# LM2596-4.net
KiCad netlist of a schematic drawn in Altium Designer
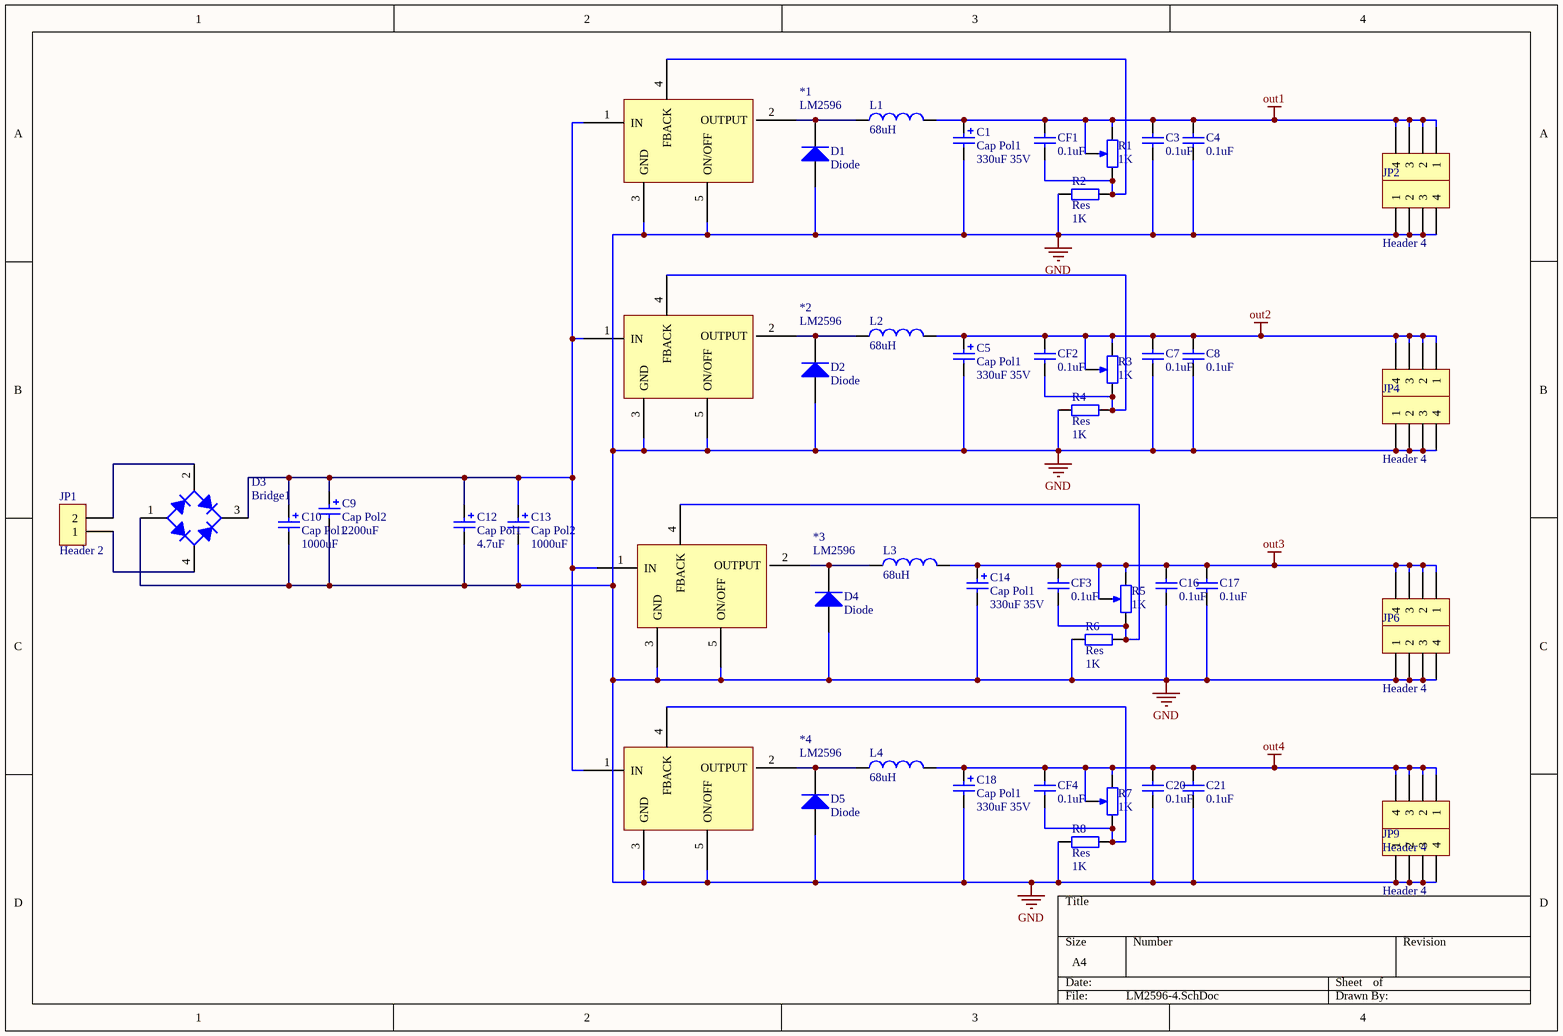
[diagram p0: LM2596-4.SchDoc]

(export (version "E")
  (design (tool "Eeschema 10.0.6"))
  (components
    (comp (ref "*1") (value "LM2596") (footprint "HDR1-5") (libsource (lib "HGH") (part "LM2596")))
    (comp (ref "*2") (value "LM2596") (footprint "HDR1-5") (libsource (lib "HGH") (part "LM2596")))
    (comp (ref "*3") (value "LM2596") (footprint "HDR1-5") (libsource (lib "HGH") (part "LM2596")))
    (comp (ref "*4") (value "LM2596") (footprint "HDR1-5") (libsource (lib "HGH") (part "LM2596")))
    (comp (ref "C1")
      (value "Cap Pol1")
      (footprint "RB0.3-0.65")
      (description "Polarized Capacitor (Radial)")
      (fields
        (field (name "MANUFACTURER") "Generic Components")
        (field (name "ALTIUM_VALUE") "330uF 35V")
        (field (name "PUBLISHER") "Altium Hobart Technology Centre")
      )
      (libsource (lib "HGH") (part "Cap Pol1"))
    )
    (comp (ref "C3")
      (value "0.1uF")
      (footprint "CC1005-0402")
      (description "Capacitor")
      (fields
        (field (name "MANUFACTURER") "Generic Components")
        (field (name "Comment") "CAP")
        (field (name "PUBLISHER") "Altium Hobart Technology Centre")
      )
      (libsource (lib "HGH") (part "CAP"))
    )
    (comp (ref "C4")
      (value "0.1uF")
      (footprint "CC1005-0402")
      (description "Capacitor")
      (fields
        (field (name "MANUFACTURER") "Generic Components")
        (field (name "Comment") "CAP")
        (field (name "PUBLISHER") "Altium Hobart Technology Centre")
      )
      (libsource (lib "HGH") (part "CAP"))
    )
    (comp (ref "C5")
      (value "Cap Pol1")
      (footprint "RB0.3-0.65")
      (description "Polarized Capacitor (Radial)")
      (fields
        (field (name "MANUFACTURER") "Generic Components")
        (field (name "ALTIUM_VALUE") "330uF 35V")
        (field (name "PUBLISHER") "Altium Hobart Technology Centre")
      )
      (libsource (lib "HGH") (part "Cap Pol1"))
    )
    (comp (ref "C7")
      (value "0.1uF")
      (footprint "CC1005-0402")
      (description "Capacitor")
      (fields
        (field (name "MANUFACTURER") "Generic Components")
        (field (name "Comment") "CAP")
        (field (name "PUBLISHER") "Altium Hobart Technology Centre")
      )
      (libsource (lib "HGH") (part "CAP"))
    )
    (comp (ref "C8")
      (value "0.1uF")
      (footprint "CC1005-0402")
      (description "Capacitor")
      (fields
        (field (name "MANUFACTURER") "Generic Components")
        (field (name "Comment") "CAP")
        (field (name "PUBLISHER") "Altium Hobart Technology Centre")
      )
      (libsource (lib "HGH") (part "CAP"))
    )
    (comp (ref "C9")
      (value "Cap Pol2")
      (footprint "RB0.3-0.65")
      (description "Polarized Capacitor (Axial)")
      (fields
        (field (name "MANUFACTURER") "Generic Components")
        (field (name "ALTIUM_VALUE") "2200uF")
        (field (name "PUBLISHER") "Altium Hobart Technology Centre")
      )
      (libsource (lib "HGH") (part "Cap Pol2"))
    )
    (comp (ref "C10")
      (value "Cap Pol1")
      (footprint "RB0.3-0.65")
      (description "Polarized Capacitor (Radial)")
      (fields
        (field (name "MANUFACTURER") "Generic Components")
        (field (name "ALTIUM_VALUE") "1000uF")
        (field (name "PUBLISHER") "Altium Hobart Technology Centre")
      )
      (libsource (lib "HGH") (part "Cap Pol1"))
    )
    (comp (ref "C12")
      (value "Cap Pol1")
      (footprint "R-0805")
      (description "Polarized Capacitor (Radial)")
      (fields
        (field (name "MANUFACTURER") "Generic Components")
        (field (name "ALTIUM_VALUE") "4.7uF")
        (field (name "PUBLISHER") "Altium Hobart Technology Centre")
      )
      (libsource (lib "HGH") (part "Cap Pol1"))
    )
    (comp (ref "C13")
      (value "Cap Pol2")
      (footprint "RB0.2-0.50")
      (description "Polarized Capacitor (Axial)")
      (fields
        (field (name "MANUFACTURER") "Generic Components")
        (field (name "ALTIUM_VALUE") "1000uF")
        (field (name "PUBLISHER") "Altium Hobart Technology Centre")
      )
      (libsource (lib "HGH") (part "Cap Pol2"))
    )
    (comp (ref "C14")
      (value "Cap Pol1")
      (footprint "RB0.3-0.65")
      (description "Polarized Capacitor (Radial)")
      (fields
        (field (name "MANUFACTURER") "Generic Components")
        (field (name "ALTIUM_VALUE") "330uF 35V")
        (field (name "PUBLISHER") "Altium Hobart Technology Centre")
      )
      (libsource (lib "HGH") (part "Cap Pol1"))
    )
    (comp (ref "C16")
      (value "0.1uF")
      (footprint "CC1005-0402")
      (description "Capacitor")
      (fields
        (field (name "MANUFACTURER") "Generic Components")
        (field (name "Comment") "CAP")
        (field (name "PUBLISHER") "Altium Hobart Technology Centre")
      )
      (libsource (lib "HGH") (part "CAP"))
    )
    (comp (ref "C17")
      (value "0.1uF")
      (footprint "CC1005-0402")
      (description "Capacitor")
      (fields
        (field (name "MANUFACTURER") "Generic Components")
        (field (name "Comment") "CAP")
        (field (name "PUBLISHER") "Altium Hobart Technology Centre")
      )
      (libsource (lib "HGH") (part "CAP"))
    )
    (comp (ref "C18")
      (value "Cap Pol1")
      (footprint "RB0.3-0.65")
      (description "Polarized Capacitor (Radial)")
      (fields
        (field (name "MANUFACTURER") "Generic Components")
        (field (name "ALTIUM_VALUE") "330uF 35V")
        (field (name "PUBLISHER") "Altium Hobart Technology Centre")
      )
      (libsource (lib "HGH") (part "Cap Pol1"))
    )
    (comp (ref "C20")
      (value "0.1uF")
      (footprint "CC1005-0402")
      (description "Capacitor")
      (fields
        (field (name "MANUFACTURER") "Generic Components")
        (field (name "Comment") "CAP")
        (field (name "PUBLISHER") "Altium Hobart Technology Centre")
      )
      (libsource (lib "HGH") (part "CAP"))
    )
    (comp (ref "C21")
      (value "0.1uF")
      (footprint "CC1005-0402")
      (description "Capacitor")
      (fields
        (field (name "MANUFACTURER") "Generic Components")
        (field (name "Comment") "CAP")
        (field (name "PUBLISHER") "Altium Hobart Technology Centre")
      )
      (libsource (lib "HGH") (part "CAP"))
    )
    (comp (ref "CF1")
      (value "0.1uF")
      (footprint "CC1005-0402")
      (description "Capacitor")
      (fields
        (field (name "MANUFACTURER") "Generic Components")
        (field (name "Comment") "CAP")
        (field (name "PUBLISHER") "Altium Hobart Technology Centre")
      )
      (libsource (lib "HGH") (part "CAP"))
    )
    (comp (ref "CF2")
      (value "0.1uF")
      (footprint "CC1005-0402")
      (description "Capacitor")
      (fields
        (field (name "MANUFACTURER") "Generic Components")
        (field (name "Comment") "CAP")
        (field (name "PUBLISHER") "Altium Hobart Technology Centre")
      )
      (libsource (lib "HGH") (part "CAP"))
    )
    (comp (ref "CF3")
      (value "0.1uF")
      (footprint "CC1005-0402")
      (description "Capacitor")
      (fields
        (field (name "MANUFACTURER") "Generic Components")
        (field (name "Comment") "CAP")
        (field (name "PUBLISHER") "Altium Hobart Technology Centre")
      )
      (libsource (lib "HGH") (part "CAP"))
    )
    (comp (ref "CF4")
      (value "0.1uF")
      (footprint "CC1005-0402")
      (description "Capacitor")
      (fields
        (field (name "MANUFACTURER") "Generic Components")
        (field (name "Comment") "CAP")
        (field (name "PUBLISHER") "Altium Hobart Technology Centre")
      )
      (libsource (lib "HGH") (part "CAP"))
    )
    (comp (ref "D1")
      (value "Diode")
      (footprint "Diode-5817")
      (description "Default Diode")
      (fields
        (field (name "MANUFACTURER") "Generic Components")
        (field (name "PUBLISHER") "Altium Hobart Technology Centre")
      )
      (libsource (lib "HGH") (part "Diode"))
    )
    (comp (ref "D2")
      (value "Diode")
      (footprint "Diode-5817")
      (description "Default Diode")
      (fields
        (field (name "MANUFACTURER") "Generic Components")
        (field (name "PUBLISHER") "Altium Hobart Technology Centre")
      )
      (libsource (lib "HGH") (part "Diode"))
    )
    (comp (ref "D3")
      (value "Bridge1")
      (footprint "qiao")
      (description "Full Wave Diode Bridge")
      (fields
        (field (name "MANUFACTURER") "Generic Components")
        (field (name "PUBLISHER") "Altium Hobart Technology Centre")
      )
      (libsource (lib "HGH") (part "Bridge1"))
    )
    (comp (ref "D4")
      (value "Diode")
      (footprint "Diode-5817")
      (description "Default Diode")
      (fields
        (field (name "MANUFACTURER") "Generic Components")
        (field (name "PUBLISHER") "Altium Hobart Technology Centre")
      )
      (libsource (lib "HGH") (part "Diode"))
    )
    (comp (ref "D5")
      (value "Diode")
      (footprint "Diode-5817")
      (description "Default Diode")
      (fields
        (field (name "MANUFACTURER") "Generic Components")
        (field (name "PUBLISHER") "Altium Hobart Technology Centre")
      )
      (libsource (lib "HGH") (part "Diode"))
    )
    (comp (ref "JP1")
      (value "Header 2")
      (footprint "H-2/2")
      (description "Header, 2-Pin")
      (fields (field (name "MANUFACTURER") "Generic Components"))
      (libsource (lib "HGH") (part "Header 2"))
    )
    (comp (ref "JP2")
      (value "Header 4")
      (footprint "HDR1-4")
      (description "Header, 4-Pin")
      (fields (field (name "MANUFACTURER") "Generic Components"))
      (libsource (lib "My SchLib") (part "Header 4"))
    )
    (comp (ref "JP3")
      (value "Header 4")
      (footprint "HDR1-4")
      (description "Header, 4-Pin")
      (fields (field (name "MANUFACTURER") "Generic Components"))
      (libsource (lib "") (part "Header 4_1"))
    )
    (comp (ref "JP4")
      (value "Header 4")
      (footprint "HDR1-4")
      (description "Header, 4-Pin")
      (fields (field (name "MANUFACTURER") "Generic Components"))
      (libsource (lib "My SchLib") (part "Header 4"))
    )
    (comp (ref "JP5")
      (value "Header 4")
      (footprint "HDR1-4")
      (description "Header, 4-Pin")
      (fields (field (name "MANUFACTURER") "Generic Components"))
      (libsource (lib "") (part "Header 4_1"))
    )
    (comp (ref "JP6")
      (value "Header 4")
      (footprint "HDR1-4")
      (description "Header, 4-Pin")
      (fields (field (name "MANUFACTURER") "Generic Components"))
      (libsource (lib "My SchLib") (part "Header 4"))
    )
    (comp (ref "JP7")
      (value "Header 4")
      (footprint "HDR1-4")
      (description "Header, 4-Pin")
      (fields (field (name "MANUFACTURER") "Generic Components"))
      (libsource (lib "") (part "Header 4_1"))
    )
    (comp (ref "JP8")
      (value "Header 4")
      (footprint "HDR1-4")
      (description "Header, 4-Pin")
      (fields (field (name "MANUFACTURER") "Generic Components"))
      (libsource (lib "My SchLib") (part "Header 4"))
    )
    (comp (ref "JP9")
      (value "Header 4")
      (footprint "HDR1-4")
      (description "Header, 4-Pin")
      (fields (field (name "MANUFACTURER") "Generic Components"))
      (libsource (lib "") (part "Header 4_1"))
    )
    (comp (ref "L1")
      (value "68uH")
      (footprint "RBL0.2")
      (description "Inductor")
      (fields
        (field (name "MANUFACTURER") "Generic Components")
        (field (name "Comment") "INDUCTOT")
        (field (name "PUBLISHER") "Altium Hobart Technology Centre")
      )
      (libsource (lib "HGH") (part "INDUCTOT"))
    )
    (comp (ref "L2")
      (value "68uH")
      (footprint "RBL0.2")
      (description "Inductor")
      (fields
        (field (name "MANUFACTURER") "Generic Components")
        (field (name "Comment") "INDUCTOT")
        (field (name "PUBLISHER") "Altium Hobart Technology Centre")
      )
      (libsource (lib "HGH") (part "INDUCTOT"))
    )
    (comp (ref "L3")
      (value "68uH")
      (footprint "RBL0.2")
      (description "Inductor")
      (fields
        (field (name "MANUFACTURER") "Generic Components")
        (field (name "Comment") "INDUCTOT")
        (field (name "PUBLISHER") "Altium Hobart Technology Centre")
      )
      (libsource (lib "HGH") (part "INDUCTOT"))
    )
    (comp (ref "L4")
      (value "68uH")
      (footprint "RBL0.2")
      (description "Inductor")
      (fields
        (field (name "MANUFACTURER") "Generic Components")
        (field (name "Comment") "INDUCTOT")
        (field (name "PUBLISHER") "Altium Hobart Technology Centre")
      )
      (libsource (lib "HGH") (part "INDUCTOT"))
    )
    (comp (ref "R1")
      (value "1K")
      (footprint "VR-S")
      (description "Potentiometer")
      (fields (field (name "Comment") "RES-Pot2"))
      (libsource (lib "HGH") (part "RES-Pot2"))
    )
    (comp (ref "R2")
      (value "Res")
      (footprint "1n4148")
      (description "Resistor")
      (fields
        (field (name "MANUFACTURER") "Generic Components")
        (field (name "ALTIUM_VALUE") "1K")
        (field (name "PUBLISHER") "Altium Hobart Technology Centre")
      )
      (libsource (lib "HGH") (part "Res"))
    )
    (comp (ref "R3")
      (value "1K")
      (footprint "VR-S")
      (description "Potentiometer")
      (fields (field (name "Comment") "RES-Pot2"))
      (libsource (lib "HGH") (part "RES-Pot2"))
    )
    (comp (ref "R4")
      (value "Res")
      (footprint "1n4148")
      (description "Resistor")
      (fields
        (field (name "MANUFACTURER") "Generic Components")
        (field (name "ALTIUM_VALUE") "1K")
        (field (name "PUBLISHER") "Altium Hobart Technology Centre")
      )
      (libsource (lib "HGH") (part "Res"))
    )
    (comp (ref "R5")
      (value "1K")
      (footprint "VR-S")
      (description "Potentiometer")
      (fields (field (name "Comment") "RES-Pot2"))
      (libsource (lib "HGH") (part "RES-Pot2"))
    )
    (comp (ref "R6")
      (value "Res")
      (footprint "1n4148")
      (description "Resistor")
      (fields
        (field (name "MANUFACTURER") "Generic Components")
        (field (name "ALTIUM_VALUE") "1K")
        (field (name "PUBLISHER") "Altium Hobart Technology Centre")
      )
      (libsource (lib "HGH") (part "Res"))
    )
    (comp (ref "R7")
      (value "1K")
      (footprint "VR-S")
      (description "Potentiometer")
      (fields (field (name "Comment") "RES-Pot2"))
      (libsource (lib "HGH") (part "RES-Pot2"))
    )
    (comp (ref "R8")
      (value "Res")
      (footprint "1n4148")
      (description "Resistor")
      (fields
        (field (name "MANUFACTURER") "Generic Components")
        (field (name "ALTIUM_VALUE") "1K")
        (field (name "PUBLISHER") "Altium Hobart Technology Centre")
      )
      (libsource (lib "HGH") (part "Res"))
    )
  )
  (nets
    (net (code "1") (name "GND") (class "Default")
      (node (ref "*1") (pin "3") (pinfunction "GND_3") (pintype "passive"))
      (node (ref "*1") (pin "5") (pinfunction "ON/OFF_5") (pintype "passive"))
      (node (ref "*2") (pin "3") (pinfunction "GND_3") (pintype "passive"))
      (node (ref "*2") (pin "5") (pinfunction "ON/OFF_5") (pintype "passive"))
      (node (ref "*3") (pin "3") (pinfunction "GND_3") (pintype "passive"))
      (node (ref "*3") (pin "5") (pinfunction "ON/OFF_5") (pintype "passive"))
      (node (ref "*4") (pin "3") (pinfunction "GND_3") (pintype "passive"))
      (node (ref "*4") (pin "5") (pinfunction "ON/OFF_5") (pintype "passive"))
      (node (ref "C1") (pin "2") (pinfunction "2_2") (pintype "passive"))
      (node (ref "C10") (pin "2") (pinfunction "2_2") (pintype "passive"))
      (node (ref "C12") (pin "2") (pinfunction "2_2") (pintype "passive"))
      (node (ref "C13") (pin "2") (pinfunction "2_2") (pintype "passive"))
      (node (ref "C14") (pin "2") (pinfunction "2_2") (pintype "passive"))
      (node (ref "C16") (pin "1") (pinfunction "1_1") (pintype "passive"))
      (node (ref "C17") (pin "1") (pinfunction "1_1") (pintype "passive"))
      (node (ref "C18") (pin "2") (pinfunction "2_2") (pintype "passive"))
      (node (ref "C20") (pin "1") (pinfunction "1_1") (pintype "passive"))
      (node (ref "C21") (pin "1") (pinfunction "1_1") (pintype "passive"))
      (node (ref "C3") (pin "1") (pinfunction "1_1") (pintype "passive"))
      (node (ref "C4") (pin "1") (pinfunction "1_1") (pintype "passive"))
      (node (ref "C5") (pin "2") (pinfunction "2_2") (pintype "passive"))
      (node (ref "C7") (pin "1") (pinfunction "1_1") (pintype "passive"))
      (node (ref "C8") (pin "1") (pinfunction "1_1") (pintype "passive"))
      (node (ref "C9") (pin "2") (pinfunction "2_2") (pintype "passive"))
      (node (ref "D1") (pin "1") (pinfunction "A_1") (pintype "passive"))
      (node (ref "D2") (pin "1") (pinfunction "A_1") (pintype "passive"))
      (node (ref "D3") (pin "1") (pinfunction "A_1") (pintype "passive"))
      (node (ref "D4") (pin "1") (pinfunction "A_1") (pintype "passive"))
      (node (ref "D5") (pin "1") (pinfunction "A_1") (pintype "passive"))
      (node (ref "JP2") (pin "1") (pinfunction "1_1") (pintype "passive"))
      (node (ref "JP2") (pin "2") (pinfunction "2_2") (pintype "passive"))
      (node (ref "JP2") (pin "3") (pinfunction "3_3") (pintype "passive"))
      (node (ref "JP2") (pin "4") (pinfunction "4_4") (pintype "passive"))
      (node (ref "JP4") (pin "1") (pinfunction "1_1") (pintype "passive"))
      (node (ref "JP4") (pin "2") (pinfunction "2_2") (pintype "passive"))
      (node (ref "JP4") (pin "3") (pinfunction "3_3") (pintype "passive"))
      (node (ref "JP4") (pin "4") (pinfunction "4_4") (pintype "passive"))
      (node (ref "JP6") (pin "1") (pinfunction "1_1") (pintype "passive"))
      (node (ref "JP6") (pin "2") (pinfunction "2_2") (pintype "passive"))
      (node (ref "JP6") (pin "3") (pinfunction "3_3") (pintype "passive"))
      (node (ref "JP6") (pin "4") (pinfunction "4_4") (pintype "passive"))
      (node (ref "JP8") (pin "1") (pinfunction "1_1") (pintype "passive"))
      (node (ref "JP8") (pin "2") (pinfunction "2_2") (pintype "passive"))
      (node (ref "JP8") (pin "3") (pinfunction "3_3") (pintype "passive"))
      (node (ref "JP8") (pin "4") (pinfunction "4_4") (pintype "passive"))
      (node (ref "R2") (pin "2") (pinfunction "2_2") (pintype "passive"))
      (node (ref "R4") (pin "2") (pinfunction "2_2") (pintype "passive"))
      (node (ref "R6") (pin "2") (pinfunction "2_2") (pintype "passive"))
      (node (ref "R8") (pin "2") (pinfunction "2_2") (pintype "passive"))
    )
    (net (code "2") (name "Net-(*1-FBACK)") (class "Default")
      (node (ref "*1") (pin "4") (pinfunction "FBACK_4") (pintype "passive"))
      (node (ref "CF1") (pin "1") (pinfunction "1_1") (pintype "passive"))
      (node (ref "R1") (pin "1") (pinfunction "BOT_1") (pintype "passive"))
      (node (ref "R2") (pin "1") (pinfunction "1_1") (pintype "passive"))
    )
    (net (code "3") (name "Net-(*1-IN)") (class "Default")
      (node (ref "*1") (pin "1") (pinfunction "IN_1") (pintype "passive"))
      (node (ref "*2") (pin "1") (pinfunction "IN_1") (pintype "passive"))
      (node (ref "*3") (pin "1") (pinfunction "IN_1") (pintype "passive"))
      (node (ref "*4") (pin "1") (pinfunction "IN_1") (pintype "passive"))
      (node (ref "C10") (pin "1") (pinfunction "1_1") (pintype "passive"))
      (node (ref "C12") (pin "1") (pinfunction "1_1") (pintype "passive"))
      (node (ref "C13") (pin "1") (pinfunction "1_1") (pintype "passive"))
      (node (ref "C9") (pin "1") (pinfunction "1_1") (pintype "passive"))
      (node (ref "D3") (pin "3") (pinfunction "K_3") (pintype "passive"))
    )
    (net (code "4") (name "Net-(*1-OUTPUT)") (class "Default")
      (node (ref "*1") (pin "2") (pinfunction "OUTPUT_2") (pintype "passive"))
      (node (ref "D1") (pin "2") (pinfunction "K_2") (pintype "passive"))
      (node (ref "L1") (pin "1") (pinfunction "1_1") (pintype "passive"))
    )
    (net (code "5") (name "Net-(*2-FBACK)") (class "Default")
      (node (ref "*2") (pin "4") (pinfunction "FBACK_4") (pintype "passive"))
      (node (ref "CF2") (pin "1") (pinfunction "1_1") (pintype "passive"))
      (node (ref "R3") (pin "1") (pinfunction "BOT_1") (pintype "passive"))
      (node (ref "R4") (pin "1") (pinfunction "1_1") (pintype "passive"))
    )
    (net (code "6") (name "Net-(*2-OUTPUT)") (class "Default")
      (node (ref "*2") (pin "2") (pinfunction "OUTPUT_2") (pintype "passive"))
      (node (ref "D2") (pin "2") (pinfunction "K_2") (pintype "passive"))
      (node (ref "L2") (pin "1") (pinfunction "1_1") (pintype "passive"))
    )
    (net (code "7") (name "Net-(*3-FBACK)") (class "Default")
      (node (ref "*3") (pin "4") (pinfunction "FBACK_4") (pintype "passive"))
      (node (ref "CF3") (pin "1") (pinfunction "1_1") (pintype "passive"))
      (node (ref "R5") (pin "1") (pinfunction "BOT_1") (pintype "passive"))
      (node (ref "R6") (pin "1") (pinfunction "1_1") (pintype "passive"))
    )
    (net (code "8") (name "Net-(*3-OUTPUT)") (class "Default")
      (node (ref "*3") (pin "2") (pinfunction "OUTPUT_2") (pintype "passive"))
      (node (ref "D4") (pin "2") (pinfunction "K_2") (pintype "passive"))
      (node (ref "L3") (pin "1") (pinfunction "1_1") (pintype "passive"))
    )
    (net (code "9") (name "Net-(*4-FBACK)") (class "Default")
      (node (ref "*4") (pin "4") (pinfunction "FBACK_4") (pintype "passive"))
      (node (ref "CF4") (pin "1") (pinfunction "1_1") (pintype "passive"))
      (node (ref "R7") (pin "1") (pinfunction "BOT_1") (pintype "passive"))
      (node (ref "R8") (pin "1") (pinfunction "1_1") (pintype "passive"))
    )
    (net (code "10") (name "Net-(*4-OUTPUT)") (class "Default")
      (node (ref "*4") (pin "2") (pinfunction "OUTPUT_2") (pintype "passive"))
      (node (ref "D5") (pin "2") (pinfunction "K_2") (pintype "passive"))
      (node (ref "L4") (pin "1") (pinfunction "1_1") (pintype "passive"))
    )
    (net (code "11") (name "Net-(D3-C-Pad2)") (class "Default")
      (node (ref "D3") (pin "2") (pinfunction "C_2") (pintype "passive"))
      (node (ref "JP1") (pin "2") (pinfunction "2_2") (pintype "passive"))
    )
    (net (code "12") (name "Net-(D3-C-Pad4)") (class "Default")
      (node (ref "D3") (pin "4") (pinfunction "C_4") (pintype "passive"))
      (node (ref "JP1") (pin "1") (pinfunction "1_1") (pintype "passive"))
    )
    (net (code "13") (name "out1") (class "Default")
      (node (ref "C1") (pin "1") (pinfunction "1_1") (pintype "passive"))
      (node (ref "C3") (pin "2") (pinfunction "2_2") (pintype "passive"))
      (node (ref "C4") (pin "2") (pinfunction "2_2") (pintype "passive"))
      (node (ref "CF1") (pin "2") (pinfunction "2_2") (pintype "passive"))
      (node (ref "JP3") (pin "1") (pinfunction "1_1") (pintype "passive"))
      (node (ref "JP3") (pin "2") (pinfunction "2_2") (pintype "passive"))
      (node (ref "JP3") (pin "3") (pinfunction "3_3") (pintype "passive"))
      (node (ref "JP3") (pin "4") (pinfunction "4_4") (pintype "passive"))
      (node (ref "L1") (pin "2") (pinfunction "2_2") (pintype "passive"))
      (node (ref "R1") (pin "2") (pinfunction "TAP_2") (pintype "passive"))
      (node (ref "R1") (pin "3") (pinfunction "TOP_3") (pintype "passive"))
    )
    (net (code "14") (name "out2") (class "Default")
      (node (ref "C5") (pin "1") (pinfunction "1_1") (pintype "passive"))
      (node (ref "C7") (pin "2") (pinfunction "2_2") (pintype "passive"))
      (node (ref "C8") (pin "2") (pinfunction "2_2") (pintype "passive"))
      (node (ref "CF2") (pin "2") (pinfunction "2_2") (pintype "passive"))
      (node (ref "JP5") (pin "1") (pinfunction "1_1") (pintype "passive"))
      (node (ref "JP5") (pin "2") (pinfunction "2_2") (pintype "passive"))
      (node (ref "JP5") (pin "3") (pinfunction "3_3") (pintype "passive"))
      (node (ref "JP5") (pin "4") (pinfunction "4_4") (pintype "passive"))
      (node (ref "L2") (pin "2") (pinfunction "2_2") (pintype "passive"))
      (node (ref "R3") (pin "2") (pinfunction "TAP_2") (pintype "passive"))
      (node (ref "R3") (pin "3") (pinfunction "TOP_3") (pintype "passive"))
    )
    (net (code "15") (name "out3") (class "Default")
      (node (ref "C14") (pin "1") (pinfunction "1_1") (pintype "passive"))
      (node (ref "C16") (pin "2") (pinfunction "2_2") (pintype "passive"))
      (node (ref "C17") (pin "2") (pinfunction "2_2") (pintype "passive"))
      (node (ref "CF3") (pin "2") (pinfunction "2_2") (pintype "passive"))
      (node (ref "JP7") (pin "1") (pinfunction "1_1") (pintype "passive"))
      (node (ref "JP7") (pin "2") (pinfunction "2_2") (pintype "passive"))
      (node (ref "JP7") (pin "3") (pinfunction "3_3") (pintype "passive"))
      (node (ref "JP7") (pin "4") (pinfunction "4_4") (pintype "passive"))
      (node (ref "L3") (pin "2") (pinfunction "2_2") (pintype "passive"))
      (node (ref "R5") (pin "2") (pinfunction "TAP_2") (pintype "passive"))
      (node (ref "R5") (pin "3") (pinfunction "TOP_3") (pintype "passive"))
    )
    (net (code "16") (name "out4") (class "Default")
      (node (ref "C18") (pin "1") (pinfunction "1_1") (pintype "passive"))
      (node (ref "C20") (pin "2") (pinfunction "2_2") (pintype "passive"))
      (node (ref "C21") (pin "2") (pinfunction "2_2") (pintype "passive"))
      (node (ref "CF4") (pin "2") (pinfunction "2_2") (pintype "passive"))
      (node (ref "JP9") (pin "1") (pinfunction "1_1") (pintype "passive"))
      (node (ref "JP9") (pin "2") (pinfunction "2_2") (pintype "passive"))
      (node (ref "JP9") (pin "3") (pinfunction "3_3") (pintype "passive"))
      (node (ref "JP9") (pin "4") (pinfunction "4_4") (pintype "passive"))
      (node (ref "L4") (pin "2") (pinfunction "2_2") (pintype "passive"))
      (node (ref "R7") (pin "2") (pinfunction "TAP_2") (pintype "passive"))
      (node (ref "R7") (pin "3") (pinfunction "TOP_3") (pintype "passive"))
    )
  )
)
